# CAN_Interface.net
KiCad netlist of a schematic drawn in Altium Designer
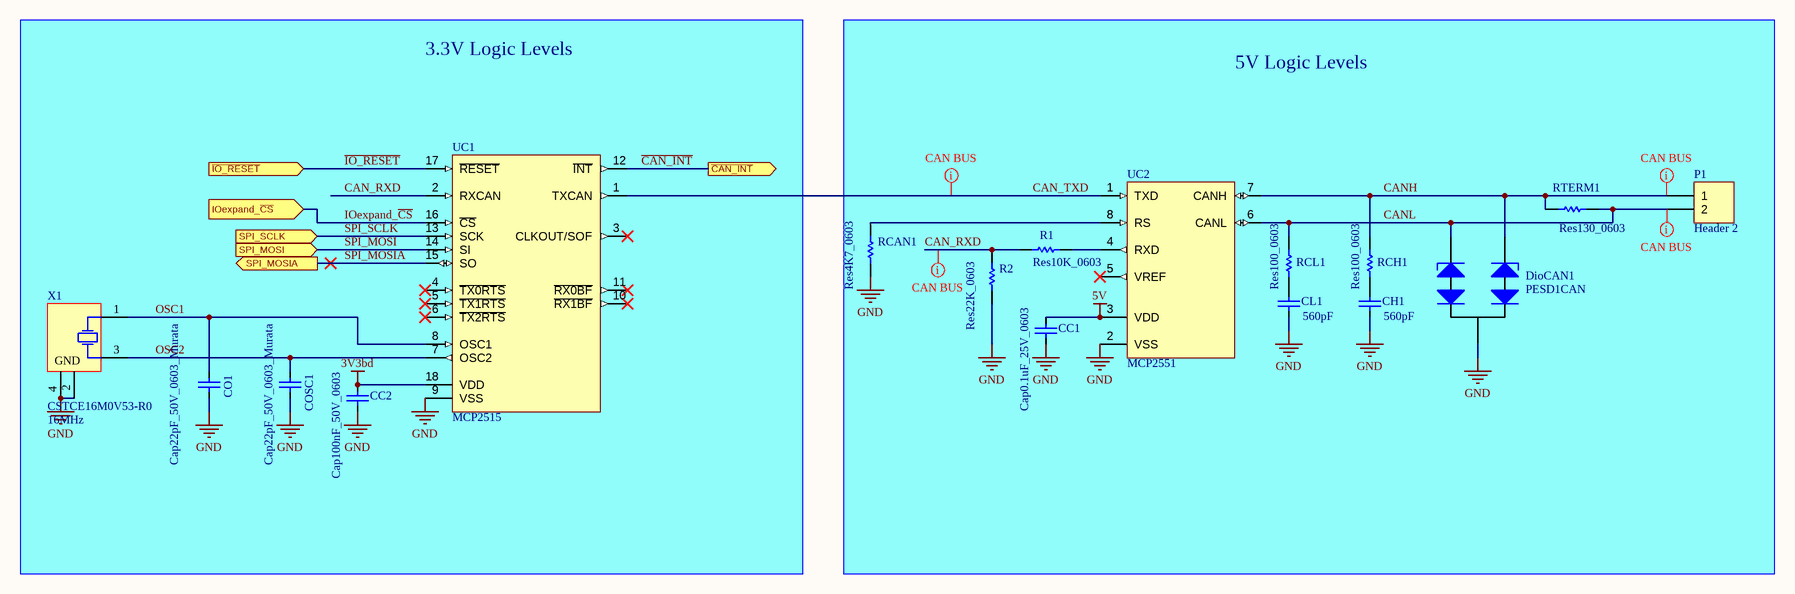
[diagram p0: CAN_Interface.SchDoc]

(export (version "E")
  (design (tool "Eeschema 10.0.6"))
  (components
    (comp (ref "CC1")
      (value "Cap0.1uF_25V_0603")
      (footprint "0603C_L")
      (libsource (lib " Advanced] Training Course - A365") (part "CAP General"))
    )
    (comp (ref "CC2")
      (value "Cap100nF_50V_0603")
      (footprint "0603C_L")
      (libsource (lib " Advanced] Training Course - A365") (part "CAP General"))
    )
    (comp (ref "CH1")
      (value "560pF")
      (footprint "0603C_L")
      (description "560pF 25V 0603")
      (fields (field (name "Comment") "CAP General"))
      (libsource (lib " Advanced] Training Course - A365") (part "CAP General"))
    )
    (comp (ref "CL1")
      (value "560pF")
      (footprint "0603C_L")
      (description "560pF 25V 0603")
      (fields (field (name "Comment") "CAP General"))
      (libsource (lib " Advanced] Training Course - A365") (part "CAP General"))
    )
    (comp (ref "CO1")
      (value "Cap22pF_50V_0603_Murata")
      (footprint "0603C_L")
      (fields (field (name "TOLERANCE") "5%"))
      (libsource (lib " Advanced] Training Course - A365") (part "CAP General"))
    )
    (comp (ref "COSC1")
      (value "Cap22pF_50V_0603_Murata")
      (footprint "0603C_L")
      (fields (field (name "TOLERANCE") "5%"))
      (libsource (lib " Advanced] Training Course - A365") (part "CAP General"))
    )
    (comp (ref "DioCAN1")
      (value "PESD1CAN")
      (footprint "SOT323")
      (description "Trans Voltage Suppressor Diode, 150W, 24V V(RWM), Bidirectional, 2 Element, Silicon")
      (fields (field (name "MANUFACTURER") "Nexperia USA Inc.") (field (name "SOURCE") "WCT.SchLib"))
      (libsource (lib " Advanced] Training Course - A365") (part "PESD1CAN"))
    )
    (comp (ref "P1")
      (value "Header 2")
      (footprint "HDR1X2")
      (description "Header, 2-Pin")
      (fields (field (name "PUBLISHER") "Altium Limited") (field (name "SOURCE") "WCT.SchLib"))
      (libsource (lib " Advanced] Training Course - A365") (part "Header 2"))
    )
    (comp (ref "R1")
      (value "Res10K_0603")
      (footprint "0603_L")
      (fields
        (field (name "MANUFACTURER") "Panasonic Electronic Components")
        (field (name "MANUFACTURER PART NUMBER") "ERJ-3GEYJ102V")
        (field (name "TOLERANCE") "5%")
        (field (name "SOURCE") "WCT.SchLib")
      )
      (libsource (lib " Advanced] Training Course - A365") (part "Resistor General"))
    )
    (comp (ref "R2")
      (value "Res22K_0603")
      (footprint "0603_L")
      (description "RES22K 0.5% 0603")
      (fields
        (field (name "MANUFACTURER") "Yageo")
        (field (name "MANUFACTURER PART NUMBER") "RT0603DRD0722KL")
        (field (name "SOURCE") "WCT.SchLib")
      )
      (libsource (lib " Advanced] Training Course - A365") (part "Resistor General"))
    )
    (comp (ref "RCAN1")
      (value "Res4K7_0603")
      (footprint "0603_L")
      (fields
        (field (name "MANUFACTURER") "Yageo")
        (field (name "TOLERANCE") "0.5%")
        (field (name "SOURCE") "WCT.SchLib")
      )
      (libsource (lib " Advanced] Training Course - A365") (part "Resistor General"))
    )
    (comp (ref "RCH1")
      (value "Res100_0603")
      (footprint "0603_L")
      (fields
        (field (name "MANUFACTURER") "Panasonic Electronic Components")
        (field (name "TOLERANCE") "5%")
        (field (name "SOURCE") "WCT.SchLib")
      )
      (libsource (lib " Advanced] Training Course - A365") (part "Resistor General"))
    )
    (comp (ref "RCL1")
      (value "Res100_0603")
      (footprint "0603_L")
      (fields
        (field (name "MANUFACTURER") "Panasonic Electronic Components")
        (field (name "TOLERANCE") "5%")
        (field (name "SOURCE") "WCT.SchLib")
      )
      (libsource (lib " Advanced] Training Course - A365") (part "Resistor General"))
    )
    (comp (ref "RTERM1")
      (value "Res130_0603")
      (footprint "0603_L")
      (fields
        (field (name "MANUFACTURER") "Panasonic Electronic Components")
        (field (name "TOLERANCE") "5%")
        (field (name "SOURCE") "WCT.SchLib")
      )
      (libsource (lib " Advanced] Training Course - A365") (part "Resistor General"))
    )
    (comp (ref "UC1")
      (value "MCP2515")
      (footprint "SOIC-SO18_M")
      (description "Stand-Alone CAN Controller With SPI Interface, 18-Pin SOIC, Extended Temperature")
      (fields
        (field (name "MANUFACTURER") "Microchip")
        (field (name "MANUFACTURER PART NUMBER") "MCP2515-E/SO")
        (field (name "AVAILABLE PREVIEW IMAGES") "2D")
        (field (name "SOURCE") "WCT.SchLib")
      )
      (libsource (lib " Advanced] Training Course - A365") (part "MCP2515"))
    )
    (comp (ref "UC2")
      (value "MCP2551")
      (footprint "SOIC-SN8_N")
      (description "High-Speed CAN Transceiver, 8-Pin SOIC, Extended Temperature")
      (fields
        (field (name "MANUFACTURER") "Microchip")
        (field (name "MANUFACTURER PART NUMBER") "MCP2551-E/SN")
        (field (name "AVAILABLE PREVIEW IMAGES") "2D")
        (field (name "SOURCE") "WCT.SchLib")
      )
      (libsource (lib " Advanced] Training Course - A365") (part "MCP2551"))
    )
    (comp (ref "X1")
      (value "CSTCE16M0V53-R0")
      (footprint "FP-ABM8-MFG")
      (description "Crystal 16MHz ±20ppm 18pF SMD-4 3.2mm x 2.5mm CSTCE16M0V53-R0 ABM8-16.000MHZ-B2-T")
      (fields
        (field (name "TOLERANCE") "20ppm")
        (field (name "FREQUENCY") "16MHz")
        (field (name "SOURCE") "WCT.SchLib")
      )
      (libsource (lib " Advanced] Training Course - A365") (part "Crystal 4Pin"))
    )
  )
  (nets
    (net (code "1") (name "/CANH") (class "Default")
      (node (ref "DioCAN1") (pin "1") (pinfunction "A_1") (pintype "passive"))
      (node (ref "P1") (pin "1") (pinfunction "1_1") (pintype "passive"))
      (node (ref "RCH1") (pin "2") (pinfunction "2_2") (pintype "passive"))
      (node (ref "RTERM1") (pin "2") (pinfunction "2_2") (pintype "passive"))
      (node (ref "UC2") (pin "7") (pinfunction "CANH_7") (pintype "bidirectional"))
    )
    (net (code "2") (name "/CANL") (class "Default")
      (node (ref "DioCAN1") (pin "2") (pinfunction "K_2") (pintype "passive"))
      (node (ref "P1") (pin "2") (pinfunction "2_2") (pintype "passive"))
      (node (ref "RCL1") (pin "2") (pinfunction "2_2") (pintype "passive"))
      (node (ref "RTERM1") (pin "1") (pinfunction "1_1") (pintype "passive"))
      (node (ref "UC2") (pin "6") (pinfunction "CANL_6") (pintype "bidirectional"))
    )
    (net (code "3") (name "/CAN_INT") (class "Default")
      (node (ref "UC1") (pin "12") (pinfunction "~{INT}_12") (pintype "output"))
    )
    (net (code "4") (name "/CAN_RXD") (class "Default")
      (node (ref "R1") (pin "2") (pinfunction "2_2") (pintype "passive"))
      (node (ref "R2") (pin "2") (pinfunction "2_2") (pintype "passive"))
      (node (ref "UC1") (pin "2") (pinfunction "RXCAN_2") (pintype "input"))
    )
    (net (code "5") (name "/CAN_TXD") (class "Default")
      (node (ref "UC1") (pin "1") (pinfunction "TXCAN_1") (pintype "output"))
      (node (ref "UC2") (pin "1") (pinfunction "TXD_1") (pintype "input"))
    )
    (net (code "6") (name "/IO_RESET") (class "Default")
      (node (ref "UC1") (pin "17") (pinfunction "~{RESET}_17") (pintype "input"))
    )
    (net (code "7") (name "/IOexpand_~{CS}") (class "Default")
      (node (ref "UC1") (pin "16") (pinfunction "~{CS}_16") (pintype "input"))
    )
    (net (code "8") (name "/OSC1") (class "Default")
      (node (ref "CO1") (pin "2") (pinfunction "2_2") (pintype "passive"))
      (node (ref "UC1") (pin "8") (pinfunction "OSC1_8") (pintype "input"))
      (node (ref "X1") (pin "1") (pinfunction "1_1") (pintype "passive"))
    )
    (net (code "9") (name "/OSC2") (class "Default")
      (node (ref "COSC1") (pin "2") (pinfunction "2_2") (pintype "passive"))
      (node (ref "UC1") (pin "7") (pinfunction "OSC2_7") (pintype "output"))
      (node (ref "X1") (pin "3") (pinfunction "3_3") (pintype "passive"))
    )
    (net (code "10") (name "/SPI_MOSI") (class "Default")
      (node (ref "UC1") (pin "14") (pinfunction "SI_14") (pintype "input"))
    )
    (net (code "11") (name "/SPI_MOSIA") (class "Default")
      (node (ref "UC1") (pin "15") (pinfunction "SO_15") (pintype "bidirectional"))
    )
    (net (code "12") (name "/SPI_SCLK") (class "Default")
      (node (ref "UC1") (pin "13") (pinfunction "SCK_13") (pintype "input"))
    )
    (net (code "13") (name "3V3bd") (class "Default")
      (node (ref "CC2") (pin "2") (pinfunction "2_2") (pintype "passive"))
      (node (ref "UC1") (pin "18") (pinfunction "VDD_18") (pintype "power_in"))
    )
    (net (code "14") (name "5V") (class "Default")
      (node (ref "CC1") (pin "2") (pinfunction "2_2") (pintype "passive"))
      (node (ref "UC2") (pin "3") (pinfunction "VDD_3") (pintype "power_in"))
    )
    (net (code "15") (name "GND") (class "Default")
      (node (ref "CC1") (pin "1") (pinfunction "1_1") (pintype "passive"))
      (node (ref "CC2") (pin "1") (pinfunction "1_1") (pintype "passive"))
      (node (ref "CH1") (pin "2") (pinfunction "2_2") (pintype "passive"))
      (node (ref "CL1") (pin "1") (pinfunction "1_1") (pintype "passive"))
      (node (ref "CO1") (pin "1") (pinfunction "1_1") (pintype "passive"))
      (node (ref "COSC1") (pin "1") (pinfunction "1_1") (pintype "passive"))
      (node (ref "DioCAN1") (pin "3") (pinfunction "3_3") (pintype "passive"))
      (node (ref "R2") (pin "1") (pinfunction "1_1") (pintype "passive"))
      (node (ref "RCAN1") (pin "1") (pinfunction "1_1") (pintype "passive"))
      (node (ref "UC1") (pin "9") (pinfunction "VSS_9") (pintype "power_in"))
      (node (ref "UC2") (pin "2") (pinfunction "VSS_2") (pintype "power_in"))
      (node (ref "X1") (pin "2") (pinfunction "GND_2") (pintype "power_in"))
      (node (ref "X1") (pin "4") (pinfunction "GND_4") (pintype "power_in"))
    )
    (net (code "16") (name "Net-(CH1-Pad1)") (class "Default")
      (node (ref "CH1") (pin "1") (pinfunction "1_1") (pintype "passive"))
      (node (ref "RCH1") (pin "1") (pinfunction "1_1") (pintype "passive"))
    )
    (net (code "17") (name "Net-(CL1-Pad2)") (class "Default")
      (node (ref "CL1") (pin "2") (pinfunction "2_2") (pintype "passive"))
      (node (ref "RCL1") (pin "1") (pinfunction "1_1") (pintype "passive"))
    )
    (net (code "18") (name "Net-(UC2-RS)") (class "Default")
      (node (ref "RCAN1") (pin "2") (pinfunction "2_2") (pintype "passive"))
      (node (ref "UC2") (pin "8") (pinfunction "RS_8") (pintype "input"))
    )
    (net (code "19") (name "Net-(UC2-RXD)") (class "Default")
      (node (ref "R1") (pin "1") (pinfunction "1_1") (pintype "passive"))
      (node (ref "UC2") (pin "4") (pinfunction "RXD_4") (pintype "output"))
    )
    (net (code "20") (name "unconnected-(UC1-CLKOUT{slash}SOF-Pad3)") (class "Default")
      (node (ref "UC1") (pin "3") (pinfunction "CLKOUT/SOF_3") (pintype "output+no_connect"))
    )
    (net (code "21") (name "unconnected-(UC1-~{RX0BF}-Pad11)") (class "Default")
      (node (ref "UC1") (pin "11") (pinfunction "~{RX0BF}_11") (pintype "output+no_connect"))
    )
    (net (code "22") (name "unconnected-(UC1-~{RX1BF}-Pad10)") (class "Default")
      (node (ref "UC1") (pin "10") (pinfunction "~{RX1BF}_10") (pintype "output+no_connect"))
    )
    (net (code "23") (name "unconnected-(UC1-~{TX0RTS}-Pad4)") (class "Default")
      (node (ref "UC1") (pin "4") (pinfunction "~{TX0RTS}_4") (pintype "input+no_connect"))
    )
    (net (code "24") (name "unconnected-(UC1-~{TX1RTS}-Pad5)") (class "Default")
      (node (ref "UC1") (pin "5") (pinfunction "~{TX1RTS}_5") (pintype "input+no_connect"))
    )
    (net (code "25") (name "unconnected-(UC1-~{TX2RTS}-Pad6)") (class "Default")
      (node (ref "UC1") (pin "6") (pinfunction "~{TX2RTS}_6") (pintype "input+no_connect"))
    )
    (net (code "26") (name "unconnected-(UC2-VREF-Pad5)") (class "Default")
      (node (ref "UC2") (pin "5") (pinfunction "VREF_5") (pintype "output+no_connect"))
    )
  )
)
